# E-06_CPU_IO_PHY.net
KiCad netlist of a schematic drawn in Altium Designer
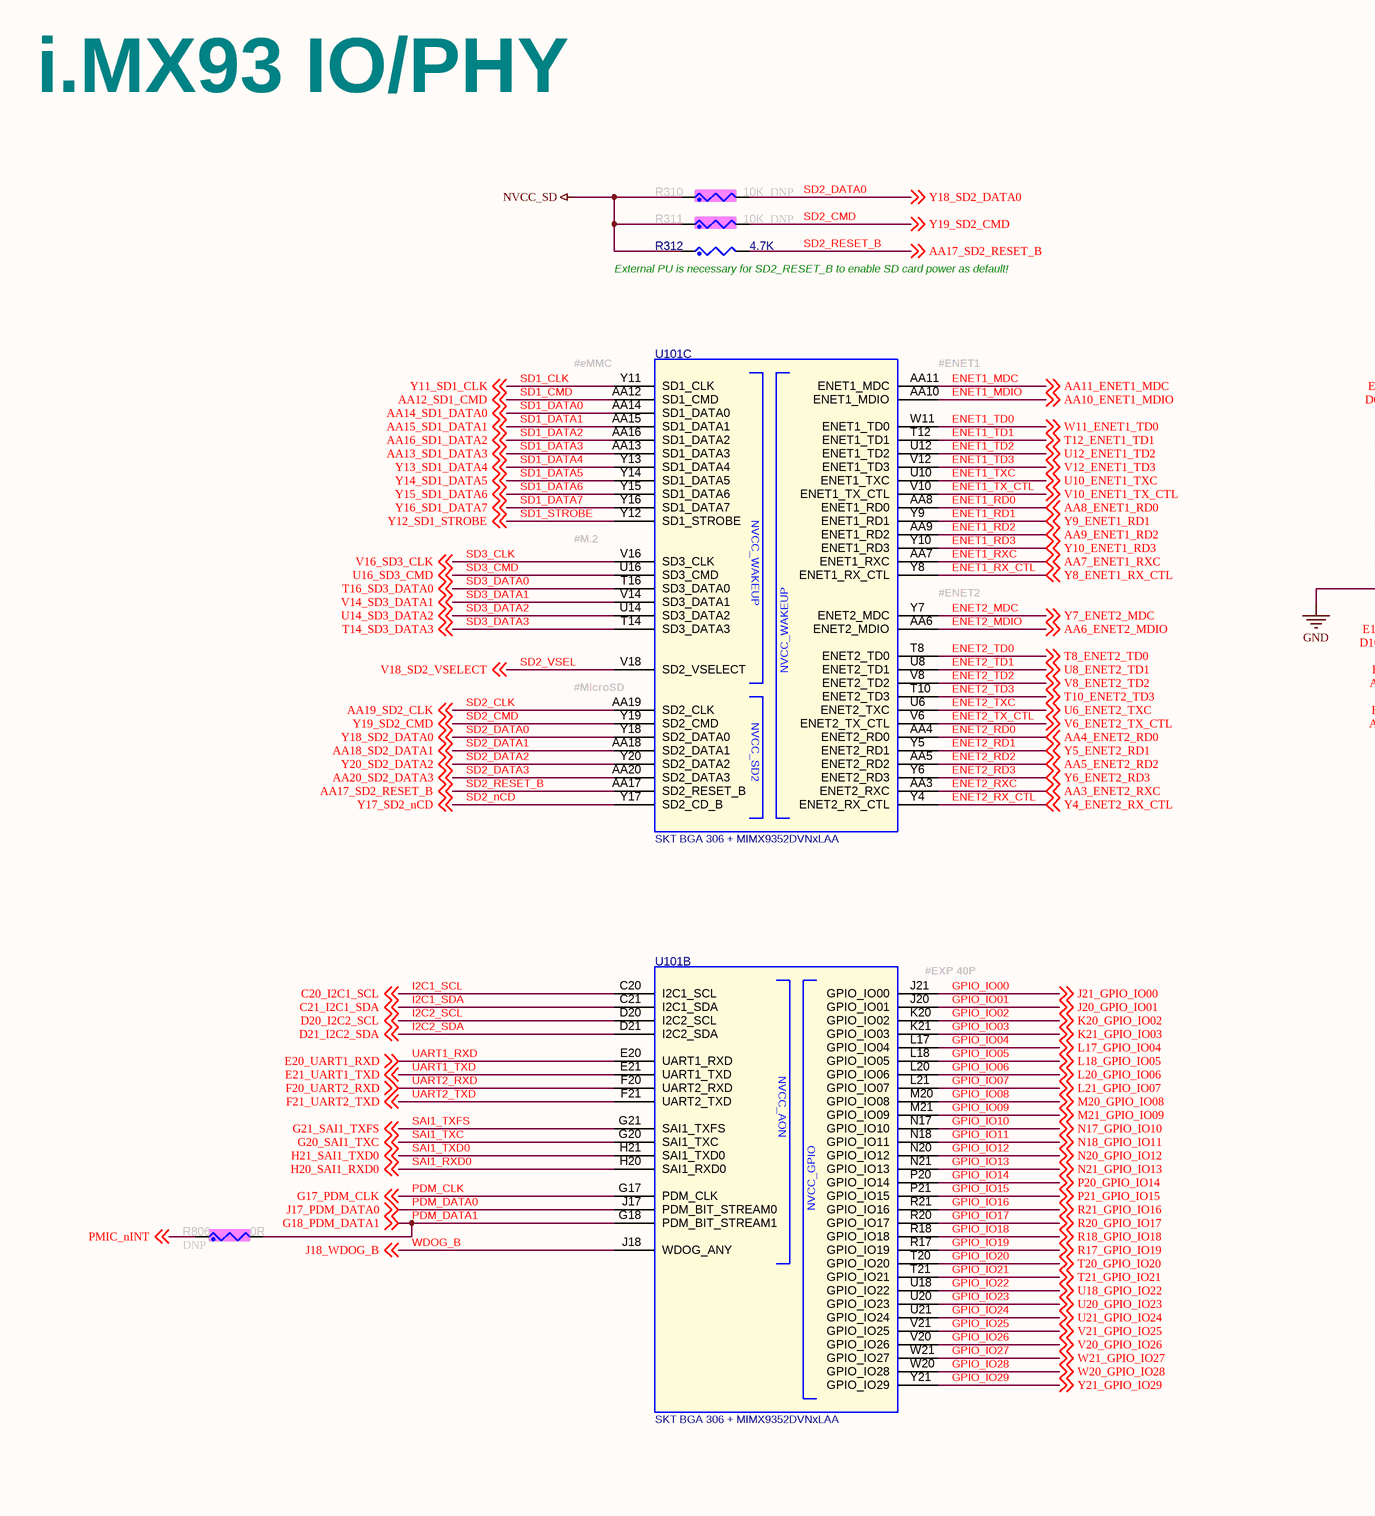
[diagram p0: E-06 CPU IO_PHY.SchDoc, left]
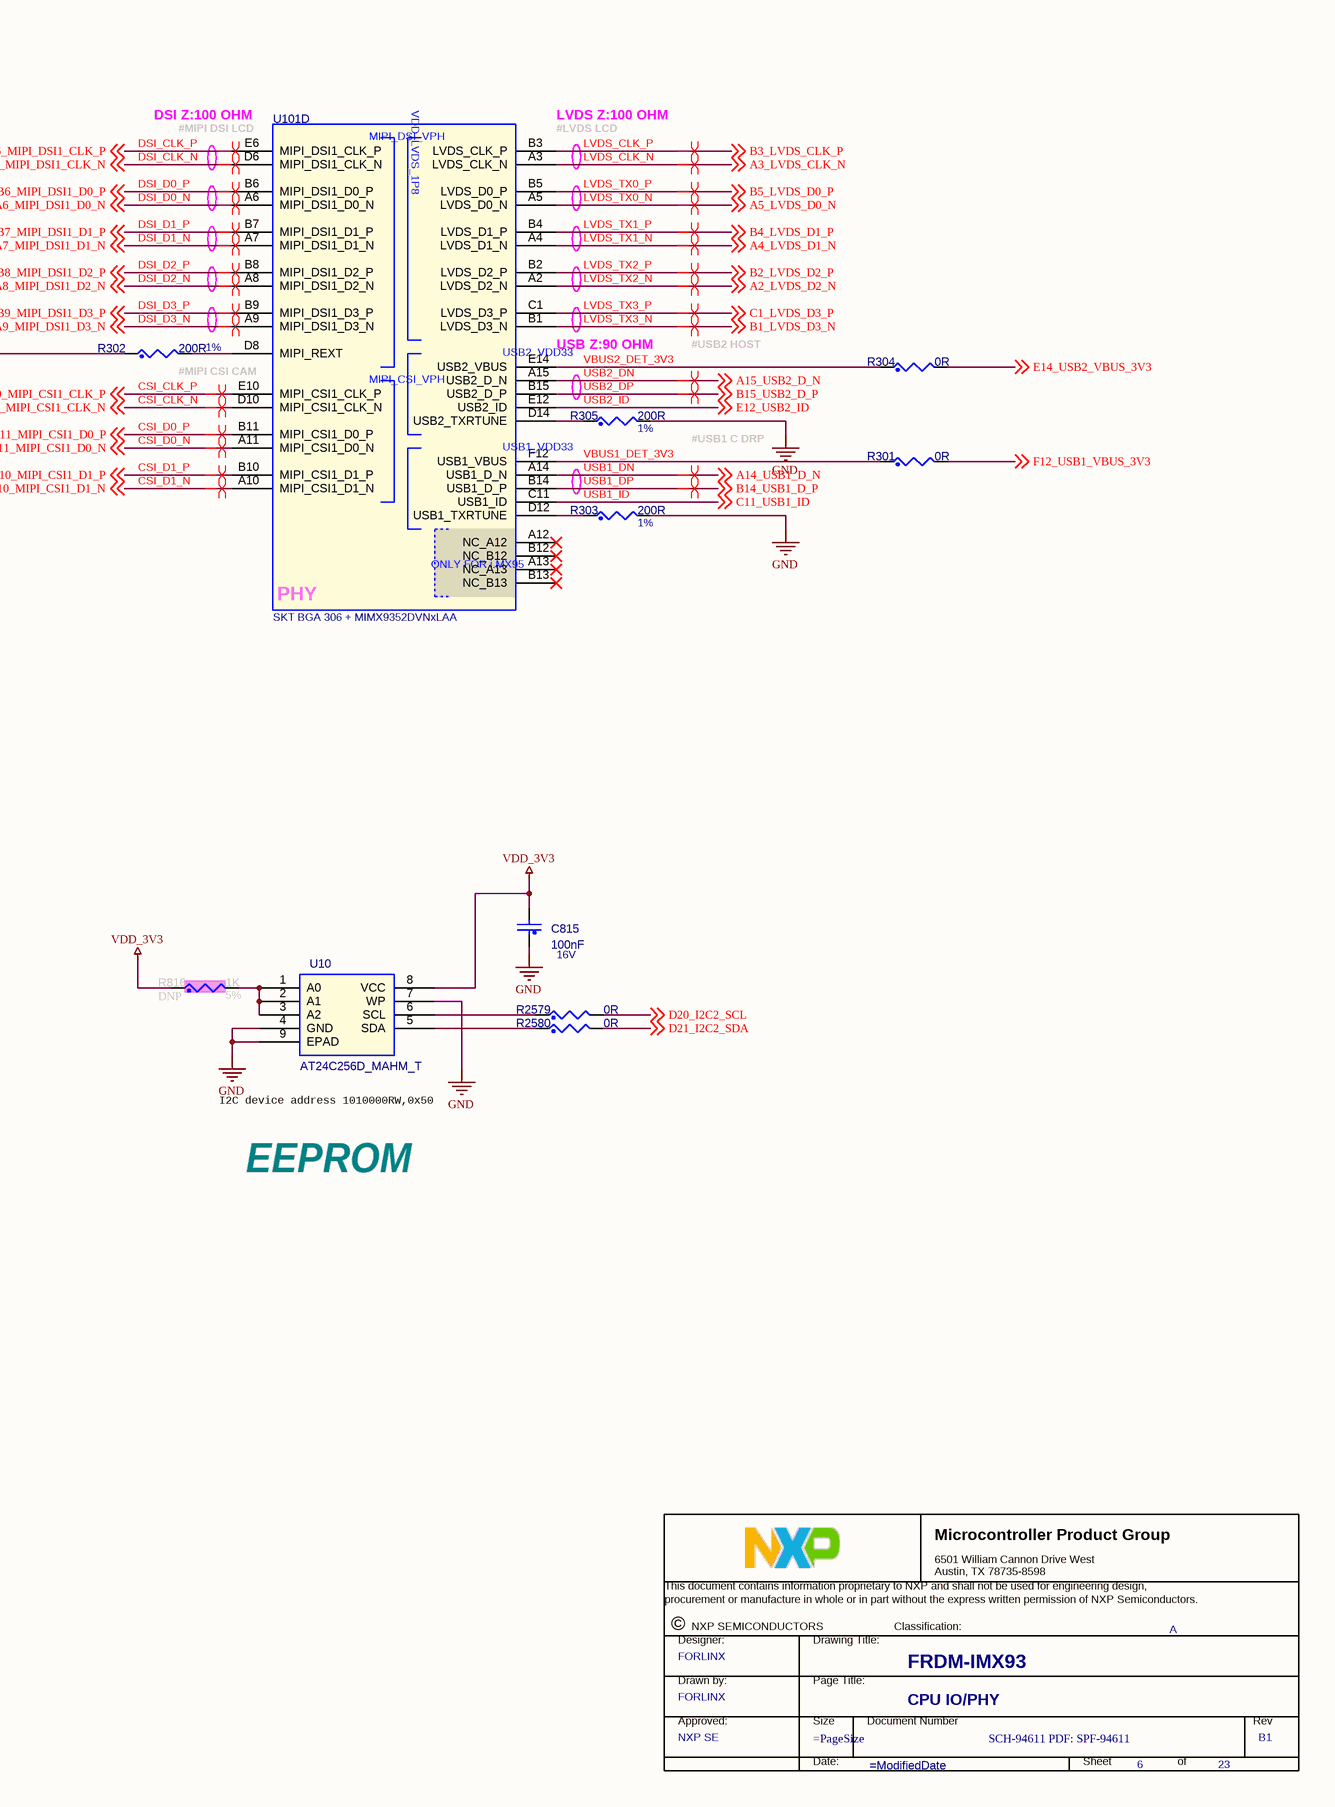
[diagram p1: E-06 CPU IO_PHY.SchDoc, right]

(export (version "E")
  (design (tool "Eeschema 10.0.6"))
  (components
    (comp (ref "C815")
      (value "100nF")
      (footprint "C0402")
      (description "0402,100nF,50V,+/-10%,X5R")
      (fields (field (name "VOLTAGE") "16V") (field (name "TOLERANCE") "10%"))
      (libsource (lib "*") (part "CAP_NP"))
    )
    (comp (ref "R301")
      (value "0R")
      (footprint "R0201")
      (description "0201,0Ohm,+/-5%")
      (libsource (lib "*") (part "RES"))
    )
    (comp (ref "R302")
      (value "200R")
      (footprint "R0201")
      (description "0201,200Ohm,+/-1%")
      (fields (field (name "VOLTAGE") "25V") (field (name "TOLERANCE") "1%"))
      (libsource (lib "*") (part "RES"))
    )
    (comp (ref "R303")
      (value "200R")
      (footprint "R0201")
      (description "0201,200Ohm,+/-1%")
      (fields (field (name "TOLERANCE") "1%") (field (name "VOLTAGE") "25V"))
      (libsource (lib "*") (part "RES"))
    )
    (comp (ref "R304")
      (value "0R")
      (footprint "R0201")
      (description "0201,0Ohm,+/-5%")
      (libsource (lib "*") (part "RES"))
    )
    (comp (ref "R305")
      (value "200R")
      (footprint "R0201")
      (description "0201,200Ohm,+/-1%")
      (fields (field (name "TOLERANCE") "1%") (field (name "VOLTAGE") "25V"))
      (libsource (lib "*") (part "RES"))
    )
    (comp (ref "R310")
      (value "10K")
      (footprint "R0402")
      (description "0402,10K,+/-1%")
      (fields (field (name "ASSY_OPT") "DNP") (field (name "TOLERANCE") "5%"))
      (libsource (lib "*") (part "RES"))
    )
    (comp (ref "R311")
      (value "10K")
      (footprint "R0402")
      (description "0402,10K,+/-1%")
      (fields (field (name "ASSY_OPT") "DNP") (field (name "TOLERANCE") "5%"))
      (libsource (lib "*") (part "RES"))
    )
    (comp (ref "R312")
      (value "4.7K")
      (footprint "R0402")
      (description "0402,4.7K,+/-1%")
      (fields (field (name "TOLERANCE") "5%") (field (name "VOLTAGE") "50V"))
      (libsource (lib "*") (part "RES"))
    )
    (comp (ref "R806")
      (value "0R")
      (footprint "R0201")
      (description "0201,0Ohm,+/-5%")
      (fields (field (name "ASSY_OPT") "DNP"))
      (libsource (lib "*") (part "RES"))
    )
    (comp (ref "R816")
      (value "1K")
      (footprint "R0402")
      (description "0402,1K,+/-1%")
      (fields (field (name "ASSY_OPT") "DNP") (field (name "TOLERANCE") "5%"))
      (libsource (lib "*") (part "RES"))
    )
    (comp (ref "R2579")
      (value "0R")
      (footprint "R0402")
      (description "0402,0Ohm,+/-1%")
      (fields (field (name "VOLTAGE") "1/16W") (field (name "TOLERANCE") "5%"))
      (libsource (lib "*") (part "RES"))
    )
    (comp (ref "R2580")
      (value "0R")
      (footprint "R0402")
      (description "0402,0Ohm,+/-1%")
      (fields (field (name "TOLERANCE") "5%") (field (name "VOLTAGE") "1/16W"))
      (libsource (lib "*") (part "RES"))
    )
    (comp (ref "U10")
      (value "AT24C256D_MAHM_T")
      (footprint "UDFN-8P")
      (description "FT24C256A-ENR-T,UDFN8")
      (libsource (lib "*") (part "AT24C64D-MA9M_0"))
    )
    (comp (ref "U101")
      (value "SKT BGA 306 + MIMX9352DVNxLAA")
      (footprint "skt_bga306_0p5_sq16p23_elast_nsp")
      (description "MIMX9352CVVXMAB,-40~105+C,11*11mm,0.5mm pitch,FCBGA,A,306pin,1.7GHz")
      (libsource (lib "") (part "MIMX9352DVNxLAA_1"))
    )
  )
  (nets
    (net (code "1") (name "/VBUS1_DET_3V3") (class "Default")
      (node (ref "R301") (pin "1") (pinfunction "1_1") (pintype "passive"))
      (node (ref "U101") (pin "F12") (pinfunction "USB1_VBUS_F12") (pintype "passive"))
    )
    (net (code "2") (name "/VBUS2_DET_3V3") (class "Default")
      (node (ref "R304") (pin "1") (pinfunction "1_1") (pintype "passive"))
      (node (ref "U101") (pin "E14") (pinfunction "USB2_VBUS_E14") (pintype "passive"))
    )
    (net (code "3") (name "A2_LVDS_D2_N") (class "Default")
      (node (ref "U101") (pin "A2") (pinfunction "LVDS_D2_N_A2") (pintype "passive"))
    )
    (net (code "4") (name "A3_LVDS_CLK_N") (class "Default")
      (node (ref "U101") (pin "A3") (pinfunction "LVDS_CLK_N_A3") (pintype "passive"))
    )
    (net (code "5") (name "A4_LVDS_D1_N") (class "Default")
      (node (ref "U101") (pin "A4") (pinfunction "LVDS_D1_N_A4") (pintype "passive"))
    )
    (net (code "6") (name "A5_LVDS_D0_N") (class "Default")
      (node (ref "U101") (pin "A5") (pinfunction "LVDS_D0_N_A5") (pintype "passive"))
    )
    (net (code "7") (name "A6_MIPI_DSI1_D0_N") (class "Default")
      (node (ref "U101") (pin "A6") (pinfunction "MIPI_DSI1_D0_N_A6") (pintype "passive"))
    )
    (net (code "8") (name "A7_MIPI_DSI1_D1_N") (class "Default")
      (node (ref "U101") (pin "A7") (pinfunction "MIPI_DSI1_D1_N_A7") (pintype "passive"))
    )
    (net (code "9") (name "A8_MIPI_DSI1_D2_N") (class "Default")
      (node (ref "U101") (pin "A8") (pinfunction "MIPI_DSI1_D2_N_A8") (pintype "passive"))
    )
    (net (code "10") (name "A9_MIPI_DSI1_D3_N") (class "Default")
      (node (ref "U101") (pin "A9") (pinfunction "MIPI_DSI1_D3_N_A9") (pintype "passive"))
    )
    (net (code "11") (name "A10_MIPI_CSI1_D1_N") (class "Default")
      (node (ref "U101") (pin "A10") (pinfunction "MIPI_CSI1_D1_N_A10") (pintype "passive"))
    )
    (net (code "12") (name "A11_MIPI_CSI1_D0_N") (class "Default")
      (node (ref "U101") (pin "A11") (pinfunction "MIPI_CSI1_D0_N_A11") (pintype "passive"))
    )
    (net (code "13") (name "A14_USB1_D_N") (class "Default")
      (node (ref "U101") (pin "A14") (pinfunction "USB1_D_N_A14") (pintype "passive"))
    )
    (net (code "14") (name "A15_USB2_D_N") (class "Default")
      (node (ref "U101") (pin "A15") (pinfunction "USB2_D_N_A15") (pintype "passive"))
    )
    (net (code "15") (name "AA3_ENET2_RXC") (class "Default")
      (node (ref "U101") (pin "AA3") (pinfunction "ENET2_RXC_AA3") (pintype "passive"))
    )
    (net (code "16") (name "AA4_ENET2_RD0") (class "Default")
      (node (ref "U101") (pin "AA4") (pinfunction "ENET2_RD0_AA4") (pintype "passive"))
    )
    (net (code "17") (name "AA5_ENET2_RD2") (class "Default")
      (node (ref "U101") (pin "AA5") (pinfunction "ENET2_RD2_AA5") (pintype "passive"))
    )
    (net (code "18") (name "AA6_ENET2_MDIO") (class "Default")
      (node (ref "U101") (pin "AA6") (pinfunction "ENET2_MDIO_AA6") (pintype "passive"))
    )
    (net (code "19") (name "AA7_ENET1_RXC") (class "Default")
      (node (ref "U101") (pin "AA7") (pinfunction "ENET1_RXC_AA7") (pintype "passive"))
    )
    (net (code "20") (name "AA8_ENET1_RD0") (class "Default")
      (node (ref "U101") (pin "AA8") (pinfunction "ENET1_RD0_AA8") (pintype "passive"))
    )
    (net (code "21") (name "AA9_ENET1_RD2") (class "Default")
      (node (ref "U101") (pin "AA9") (pinfunction "ENET1_RD2_AA9") (pintype "passive"))
    )
    (net (code "22") (name "AA10_ENET1_MDIO") (class "Default")
      (node (ref "U101") (pin "AA10") (pinfunction "ENET1_MDIO_AA10") (pintype "passive"))
    )
    (net (code "23") (name "AA11_ENET1_MDC") (class "Default")
      (node (ref "U101") (pin "AA11") (pinfunction "ENET1_MDC_AA11") (pintype "passive"))
    )
    (net (code "24") (name "AA12_SD1_CMD") (class "Default")
      (node (ref "U101") (pin "AA12") (pinfunction "SD1_CMD_AA12") (pintype "passive"))
    )
    (net (code "25") (name "AA13_SD1_DATA3") (class "Default")
      (node (ref "U101") (pin "AA13") (pinfunction "SD1_DATA3_AA13") (pintype "passive"))
    )
    (net (code "26") (name "AA14_SD1_DATA0") (class "Default")
      (node (ref "U101") (pin "AA14") (pinfunction "SD1_DATA0_AA14") (pintype "passive"))
    )
    (net (code "27") (name "AA15_SD1_DATA1") (class "Default")
      (node (ref "U101") (pin "AA15") (pinfunction "SD1_DATA1_AA15") (pintype "passive"))
    )
    (net (code "28") (name "AA16_SD1_DATA2") (class "Default")
      (node (ref "U101") (pin "AA16") (pinfunction "SD1_DATA2_AA16") (pintype "passive"))
    )
    (net (code "29") (name "AA17_SD2_RESET_B") (class "Default")
      (node (ref "R312") (pin "2") (pinfunction "2_2") (pintype "passive"))
      (node (ref "U101") (pin "AA17") (pinfunction "SD2_RESET_B_AA17") (pintype "passive"))
    )
    (net (code "30") (name "AA18_SD2_DATA1") (class "Default")
      (node (ref "U101") (pin "AA18") (pinfunction "SD2_DATA1_AA18") (pintype "passive"))
    )
    (net (code "31") (name "AA19_SD2_CLK") (class "Default")
      (node (ref "U101") (pin "AA19") (pinfunction "SD2_CLK_AA19") (pintype "passive"))
    )
    (net (code "32") (name "AA20_SD2_DATA3") (class "Default")
      (node (ref "U101") (pin "AA20") (pinfunction "SD2_DATA3_AA20") (pintype "passive"))
    )
    (net (code "33") (name "B1_LVDS_D3_N") (class "Default")
      (node (ref "U101") (pin "B1") (pinfunction "LVDS_D3_N_B1") (pintype "passive"))
    )
    (net (code "34") (name "B2_LVDS_D2_P") (class "Default")
      (node (ref "U101") (pin "B2") (pinfunction "LVDS_D2_P_B2") (pintype "passive"))
    )
    (net (code "35") (name "B3_LVDS_CLK_P") (class "Default")
      (node (ref "U101") (pin "B3") (pinfunction "LVDS_CLK_P_B3") (pintype "passive"))
    )
    (net (code "36") (name "B4_LVDS_D1_P") (class "Default")
      (node (ref "U101") (pin "B4") (pinfunction "LVDS_D1_P_B4") (pintype "passive"))
    )
    (net (code "37") (name "B5_LVDS_D0_P") (class "Default")
      (node (ref "U101") (pin "B5") (pinfunction "LVDS_D0_P_B5") (pintype "passive"))
    )
    (net (code "38") (name "B6_MIPI_DSI1_D0_P") (class "Default")
      (node (ref "U101") (pin "B6") (pinfunction "MIPI_DSI1_D0_P_B6") (pintype "passive"))
    )
    (net (code "39") (name "B7_MIPI_DSI1_D1_P") (class "Default")
      (node (ref "U101") (pin "B7") (pinfunction "MIPI_DSI1_D1_P_B7") (pintype "passive"))
    )
    (net (code "40") (name "B8_MIPI_DSI1_D2_P") (class "Default")
      (node (ref "U101") (pin "B8") (pinfunction "MIPI_DSI1_D2_P_B8") (pintype "passive"))
    )
    (net (code "41") (name "B9_MIPI_DSI1_D3_P") (class "Default")
      (node (ref "U101") (pin "B9") (pinfunction "MIPI_DSI1_D3_P_B9") (pintype "passive"))
    )
    (net (code "42") (name "B10_MIPI_CSI1_D1_P") (class "Default")
      (node (ref "U101") (pin "B10") (pinfunction "MIPI_CSI1_D1_P_B10") (pintype "passive"))
    )
    (net (code "43") (name "B11_MIPI_CSI1_D0_P") (class "Default")
      (node (ref "U101") (pin "B11") (pinfunction "MIPI_CSI1_D0_P_B11") (pintype "passive"))
    )
    (net (code "44") (name "B14_USB1_D_P") (class "Default")
      (node (ref "U101") (pin "B14") (pinfunction "USB1_D_P_B14") (pintype "passive"))
    )
    (net (code "45") (name "B15_USB2_D_P") (class "Default")
      (node (ref "U101") (pin "B15") (pinfunction "USB2_D_P_B15") (pintype "passive"))
    )
    (net (code "46") (name "C1_LVDS_D3_P") (class "Default")
      (node (ref "U101") (pin "C1") (pinfunction "LVDS_D3_P_C1") (pintype "passive"))
    )
    (net (code "47") (name "C11_USB1_ID") (class "Default")
      (node (ref "U101") (pin "C11") (pinfunction "USB1_ID_C11") (pintype "passive"))
    )
    (net (code "48") (name "C20_I2C1_SCL") (class "Default")
      (node (ref "U101") (pin "C20") (pinfunction "I2C1_SCL_C20") (pintype "passive"))
    )
    (net (code "49") (name "C21_I2C1_SDA") (class "Default")
      (node (ref "U101") (pin "C21") (pinfunction "I2C1_SDA_C21") (pintype "passive"))
    )
    (net (code "50") (name "D6_MIPI_DSI1_CLK_N") (class "Default")
      (node (ref "U101") (pin "D6") (pinfunction "MIPI_DSI1_CLK_N_D6") (pintype "passive"))
    )
    (net (code "51") (name "D10_MIPI_CSI1_CLK_N") (class "Default")
      (node (ref "U101") (pin "D10") (pinfunction "MIPI_CSI1_CLK_N_D10") (pintype "passive"))
    )
    (net (code "52") (name "D20_I2C2_SCL") (class "Default")
      (node (ref "R2579") (pin "2") (pinfunction "2_2") (pintype "passive"))
      (node (ref "U101") (pin "D20") (pinfunction "I2C2_SCL_D20") (pintype "passive"))
    )
    (net (code "53") (name "D21_I2C2_SDA") (class "Default")
      (node (ref "R2580") (pin "2") (pinfunction "2_2") (pintype "passive"))
      (node (ref "U101") (pin "D21") (pinfunction "I2C2_SDA_D21") (pintype "passive"))
    )
    (net (code "54") (name "E6_MIPI_DSI1_CLK_P") (class "Default")
      (node (ref "U101") (pin "E6") (pinfunction "MIPI_DSI1_CLK_P_E6") (pintype "passive"))
    )
    (net (code "55") (name "E10_MIPI_CSI1_CLK_P") (class "Default")
      (node (ref "U101") (pin "E10") (pinfunction "MIPI_CSI1_CLK_P_E10") (pintype "passive"))
    )
    (net (code "56") (name "E12_USB2_ID") (class "Default")
      (node (ref "U101") (pin "E12") (pinfunction "USB2_ID_E12") (pintype "passive"))
    )
    (net (code "57") (name "E14_USB2_VBUS_3V3") (class "Default")
      (node (ref "R304") (pin "2") (pinfunction "2_2") (pintype "passive"))
    )
    (net (code "58") (name "E20_UART1_RXD") (class "Default")
      (node (ref "U101") (pin "E20") (pinfunction "UART1_RXD_E20") (pintype "passive"))
    )
    (net (code "59") (name "E21_UART1_TXD") (class "Default")
      (node (ref "U101") (pin "E21") (pinfunction "UART1_TXD_E21") (pintype "passive"))
    )
    (net (code "60") (name "F12_USB1_VBUS_3V3") (class "Default")
      (node (ref "R301") (pin "2") (pinfunction "2_2") (pintype "passive"))
    )
    (net (code "61") (name "F20_UART2_RXD") (class "Default")
      (node (ref "U101") (pin "F20") (pinfunction "UART2_RXD_F20") (pintype "passive"))
    )
    (net (code "62") (name "F21_UART2_TXD") (class "Default")
      (node (ref "U101") (pin "F21") (pinfunction "UART2_TXD_F21") (pintype "passive"))
    )
    (net (code "63") (name "G17_PDM_CLK") (class "Default")
      (node (ref "U101") (pin "G17") (pinfunction "PDM_CLK_G17") (pintype "passive"))
    )
    (net (code "64") (name "G18_PDM_DATA1") (class "Default")
      (node (ref "R806") (pin "2") (pinfunction "2_2") (pintype "passive"))
      (node (ref "U101") (pin "G18") (pinfunction "PDM_BIT_STREAM1_G18") (pintype "passive"))
    )
    (net (code "65") (name "G20_SAI1_TXC") (class "Default")
      (node (ref "U101") (pin "G20") (pinfunction "SAI1_TXC_G20") (pintype "passive"))
    )
    (net (code "66") (name "G21_SAI1_TXFS") (class "Default")
      (node (ref "U101") (pin "G21") (pinfunction "SAI1_TXFS_G21") (pintype "passive"))
    )
    (net (code "67") (name "GND") (class "Default")
      (node (ref "C815") (pin "1") (pinfunction "1_1") (pintype "passive"))
      (node (ref "R302") (pin "1") (pinfunction "1_1") (pintype "passive"))
      (node (ref "R303") (pin "2") (pinfunction "2_2") (pintype "passive"))
      (node (ref "R305") (pin "2") (pinfunction "2_2") (pintype "passive"))
      (node (ref "U10") (pin "4") (pinfunction "GND_4") (pintype "passive"))
      (node (ref "U10") (pin "7") (pinfunction "WP_7") (pintype "passive"))
      (node (ref "U10") (pin "9") (pinfunction "EPAD_9") (pintype "passive"))
    )
    (net (code "68") (name "H20_SAI1_RXD0") (class "Default")
      (node (ref "U101") (pin "H20") (pinfunction "SAI1_RXD0_H20") (pintype "passive"))
    )
    (net (code "69") (name "H21_SAI1_TXD0") (class "Default")
      (node (ref "U101") (pin "H21") (pinfunction "SAI1_TXD0_H21") (pintype "passive"))
    )
    (net (code "70") (name "J17_PDM_DATA0") (class "Default")
      (node (ref "U101") (pin "J17") (pinfunction "PDM_BIT_STREAM0_J17") (pintype "passive"))
    )
    (net (code "71") (name "J18_WDOG_B") (class "Default")
      (node (ref "U101") (pin "J18") (pinfunction "WDOG_ANY_J18") (pintype "passive"))
    )
    (net (code "72") (name "J20_GPIO_IO01") (class "Default")
      (node (ref "U101") (pin "J20") (pinfunction "GPIO_IO01_J20") (pintype "passive"))
    )
    (net (code "73") (name "J21_GPIO_IO00") (class "Default")
      (node (ref "U101") (pin "J21") (pinfunction "GPIO_IO00_J21") (pintype "passive"))
    )
    (net (code "74") (name "K20_GPIO_IO02") (class "Default")
      (node (ref "U101") (pin "K20") (pinfunction "GPIO_IO02_K20") (pintype "passive"))
    )
    (net (code "75") (name "K21_GPIO_IO03") (class "Default")
      (node (ref "U101") (pin "K21") (pinfunction "GPIO_IO03_K21") (pintype "passive"))
    )
    (net (code "76") (name "L17_GPIO_IO04") (class "Default")
      (node (ref "U101") (pin "L17") (pinfunction "GPIO_IO04_L17") (pintype "passive"))
    )
    (net (code "77") (name "L18_GPIO_IO05") (class "Default")
      (node (ref "U101") (pin "L18") (pinfunction "GPIO_IO05_L18") (pintype "passive"))
    )
    (net (code "78") (name "L20_GPIO_IO06") (class "Default")
      (node (ref "U101") (pin "L20") (pinfunction "GPIO_IO06_L20") (pintype "passive"))
    )
    (net (code "79") (name "L21_GPIO_IO07") (class "Default")
      (node (ref "U101") (pin "L21") (pinfunction "GPIO_IO07_L21") (pintype "passive"))
    )
    (net (code "80") (name "M20_GPIO_IO08") (class "Default")
      (node (ref "U101") (pin "M20") (pinfunction "GPIO_IO08_M20") (pintype "passive"))
    )
    (net (code "81") (name "M21_GPIO_IO09") (class "Default")
      (node (ref "U101") (pin "M21") (pinfunction "GPIO_IO09_M21") (pintype "passive"))
    )
    (net (code "82") (name "N17_GPIO_IO10") (class "Default")
      (node (ref "U101") (pin "N17") (pinfunction "GPIO_IO10_N17") (pintype "passive"))
    )
    (net (code "83") (name "N18_GPIO_IO11") (class "Default")
      (node (ref "U101") (pin "N18") (pinfunction "GPIO_IO11_N18") (pintype "passive"))
    )
    (net (code "84") (name "N20_GPIO_IO12") (class "Default")
      (node (ref "U101") (pin "N20") (pinfunction "GPIO_IO12_N20") (pintype "passive"))
    )
    (net (code "85") (name "N21_GPIO_IO13") (class "Default")
      (node (ref "U101") (pin "N21") (pinfunction "GPIO_IO13_N21") (pintype "passive"))
    )
    (net (code "86") (name "NVCC_SD") (class "Default")
      (node (ref "R310") (pin "1") (pinfunction "1_1") (pintype "passive"))
      (node (ref "R311") (pin "1") (pinfunction "1_1") (pintype "passive"))
      (node (ref "R312") (pin "1") (pinfunction "1_1") (pintype "passive"))
    )
    (net (code "87") (name "Net-(U10-A0)") (class "Default")
      (node (ref "R816") (pin "2") (pinfunction "2_2") (pintype "passive"))
      (node (ref "U10") (pin "1") (pinfunction "A0_1") (pintype "passive"))
      (node (ref "U10") (pin "2") (pinfunction "A1_2") (pintype "passive"))
      (node (ref "U10") (pin "3") (pinfunction "A2_3") (pintype "passive"))
    )
    (net (code "88") (name "Net-(U10-SCL)") (class "Default")
      (node (ref "R2579") (pin "1") (pinfunction "1_1") (pintype "passive"))
      (node (ref "U10") (pin "6") (pinfunction "SCL_6") (pintype "passive"))
    )
    (net (code "89") (name "Net-(U10-SDA)") (class "Default")
      (node (ref "R2580") (pin "1") (pinfunction "1_1") (pintype "passive"))
      (node (ref "U10") (pin "5") (pinfunction "SDA_5") (pintype "passive"))
    )
    (net (code "90") (name "Net-(U101D-MIPI_REXT)") (class "Default")
      (node (ref "R302") (pin "2") (pinfunction "2_2") (pintype "passive"))
      (node (ref "U101") (pin "D8") (pinfunction "MIPI_REXT_D8") (pintype "passive"))
    )
    (net (code "91") (name "Net-(U101D-USB1_TXRTUNE)") (class "Default")
      (node (ref "R303") (pin "1") (pinfunction "1_1") (pintype "passive"))
      (node (ref "U101") (pin "D12") (pinfunction "USB1_TXRTUNE_D12") (pintype "passive"))
    )
    (net (code "92") (name "Net-(U101D-USB2_TXRTUNE)") (class "Default")
      (node (ref "R305") (pin "1") (pinfunction "1_1") (pintype "passive"))
      (node (ref "U101") (pin "D14") (pinfunction "USB2_TXRTUNE_D14") (pintype "passive"))
    )
    (net (code "93") (name "P20_GPIO_IO14") (class "Default")
      (node (ref "U101") (pin "P20") (pinfunction "GPIO_IO14_P20") (pintype "passive"))
    )
    (net (code "94") (name "P21_GPIO_IO15") (class "Default")
      (node (ref "U101") (pin "P21") (pinfunction "GPIO_IO15_P21") (pintype "passive"))
    )
    (net (code "95") (name "PMIC_nINT") (class "Default")
      (node (ref "R806") (pin "1") (pinfunction "1_1") (pintype "passive"))
    )
    (net (code "96") (name "R17_GPIO_IO19") (class "Default")
      (node (ref "U101") (pin "R17") (pinfunction "GPIO_IO19_R17") (pintype "passive"))
    )
    (net (code "97") (name "R18_GPIO_IO18") (class "Default")
      (node (ref "U101") (pin "R18") (pinfunction "GPIO_IO18_R18") (pintype "passive"))
    )
    (net (code "98") (name "R20_GPIO_IO17") (class "Default")
      (node (ref "U101") (pin "R20") (pinfunction "GPIO_IO17_R20") (pintype "passive"))
    )
    (net (code "99") (name "R21_GPIO_IO16") (class "Default")
      (node (ref "U101") (pin "R21") (pinfunction "GPIO_IO16_R21") (pintype "passive"))
    )
    (net (code "100") (name "T8_ENET2_TD0") (class "Default")
      (node (ref "U101") (pin "T8") (pinfunction "ENET2_TD0_T8") (pintype "passive"))
    )
    (net (code "101") (name "T10_ENET2_TD3") (class "Default")
      (node (ref "U101") (pin "T10") (pinfunction "ENET2_TD3_T10") (pintype "passive"))
    )
    (net (code "102") (name "T12_ENET1_TD1") (class "Default")
      (node (ref "U101") (pin "T12") (pinfunction "ENET1_TD1_T12") (pintype "passive"))
    )
    (net (code "103") (name "T14_SD3_DATA3") (class "Default")
      (node (ref "U101") (pin "T14") (pinfunction "SD3_DATA3_T14") (pintype "passive"))
    )
    (net (code "104") (name "T16_SD3_DATA0") (class "Default")
      (node (ref "U101") (pin "T16") (pinfunction "SD3_DATA0_T16") (pintype "passive"))
    )
    (net (code "105") (name "T20_GPIO_IO20") (class "Default")
      (node (ref "U101") (pin "T20") (pinfunction "GPIO_IO20_T20") (pintype "passive"))
    )
    (net (code "106") (name "T21_GPIO_IO21") (class "Default")
      (node (ref "U101") (pin "T21") (pinfunction "GPIO_IO21_T21") (pintype "passive"))
    )
    (net (code "107") (name "U6_ENET2_TXC") (class "Default")
      (node (ref "U101") (pin "U6") (pinfunction "ENET2_TXC_U6") (pintype "passive"))
    )
    (net (code "108") (name "U8_ENET2_TD1") (class "Default")
      (node (ref "U101") (pin "U8") (pinfunction "ENET2_TD1_U8") (pintype "passive"))
    )
    (net (code "109") (name "U10_ENET1_TXC") (class "Default")
      (node (ref "U101") (pin "U10") (pinfunction "ENET1_TXC_U10") (pintype "passive"))
    )
    (net (code "110") (name "U12_ENET1_TD2") (class "Default")
      (node (ref "U101") (pin "U12") (pinfunction "ENET1_TD2_U12") (pintype "passive"))
    )
    (net (code "111") (name "U14_SD3_DATA2") (class "Default")
      (node (ref "U101") (pin "U14") (pinfunction "SD3_DATA2_U14") (pintype "passive"))
    )
    (net (code "112") (name "U16_SD3_CMD") (class "Default")
      (node (ref "U101") (pin "U16") (pinfunction "SD3_CMD_U16") (pintype "passive"))
    )
    (net (code "113") (name "U18_GPIO_IO22") (class "Default")
      (node (ref "U101") (pin "U18") (pinfunction "GPIO_IO22_U18") (pintype "passive"))
    )
    (net (code "114") (name "U20_GPIO_IO23") (class "Default")
      (node (ref "U101") (pin "U20") (pinfunction "GPIO_IO23_U20") (pintype "passive"))
    )
    (net (code "115") (name "U21_GPIO_IO24") (class "Default")
      (node (ref "U101") (pin "U21") (pinfunction "GPIO_IO24_U21") (pintype "passive"))
    )
    (net (code "116") (name "V6_ENET2_TX_CTL") (class "Default")
      (node (ref "U101") (pin "V6") (pinfunction "ENET2_TX_CTL_V6") (pintype "passive"))
    )
    (net (code "117") (name "V8_ENET2_TD2") (class "Default")
      (node (ref "U101") (pin "V8") (pinfunction "ENET2_TD2_V8") (pintype "passive"))
    )
    (net (code "118") (name "V10_ENET1_TX_CTL") (class "Default")
      (node (ref "U101") (pin "V10") (pinfunction "ENET1_TX_CTL_V10") (pintype "passive"))
    )
    (net (code "119") (name "V12_ENET1_TD3") (class "Default")
      (node (ref "U101") (pin "V12") (pinfunction "ENET1_TD3_V12") (pintype "passive"))
    )
    (net (code "120") (name "V14_SD3_DATA1") (class "Default")
      (node (ref "U101") (pin "V14") (pinfunction "SD3_DATA1_V14") (pintype "passive"))
    )
    (net (code "121") (name "V16_SD3_CLK") (class "Default")
      (node (ref "U101") (pin "V16") (pinfunction "SD3_CLK_V16") (pintype "passive"))
    )
    (net (code "122") (name "V18_SD2_VSELECT") (class "Default")
      (node (ref "U101") (pin "V18") (pinfunction "SD2_VSELECT_V18") (pintype "passive"))
    )
    (net (code "123") (name "V20_GPIO_IO26") (class "Default")
      (node (ref "U101") (pin "V20") (pinfunction "GPIO_IO26_V20") (pintype "passive"))
    )
    (net (code "124") (name "V21_GPIO_IO25") (class "Default")
      (node (ref "U101") (pin "V21") (pinfunction "GPIO_IO25_V21") (pintype "passive"))
    )
    (net (code "125") (name "VDD_3V3") (class "Default")
      (node (ref "C815") (pin "2") (pinfunction "2_2") (pintype "passive"))
      (node (ref "R816") (pin "1") (pinfunction "1_1") (pintype "passive"))
      (node (ref "U10") (pin "8") (pinfunction "VCC_8") (pintype "passive"))
    )
    (net (code "126") (name "W11_ENET1_TD0") (class "Default")
      (node (ref "U101") (pin "W11") (pinfunction "ENET1_TD0_W11") (pintype "passive"))
    )
    (net (code "127") (name "W20_GPIO_IO28") (class "Default")
      (node (ref "U101") (pin "W20") (pinfunction "GPIO_IO28_W20") (pintype "passive"))
    )
    (net (code "128") (name "W21_GPIO_IO27") (class "Default")
      (node (ref "U101") (pin "W21") (pinfunction "GPIO_IO27_W21") (pintype "passive"))
    )
    (net (code "129") (name "Y4_ENET2_RX_CTL") (class "Default")
      (node (ref "U101") (pin "Y4") (pinfunction "ENET2_RX_CTL_Y4") (pintype "passive"))
    )
    (net (code "130") (name "Y5_ENET2_RD1") (class "Default")
      (node (ref "U101") (pin "Y5") (pinfunction "ENET2_RD1_Y5") (pintype "passive"))
    )
    (net (code "131") (name "Y6_ENET2_RD3") (class "Default")
      (node (ref "U101") (pin "Y6") (pinfunction "ENET2_RD3_Y6") (pintype "passive"))
    )
    (net (code "132") (name "Y7_ENET2_MDC") (class "Default")
      (node (ref "U101") (pin "Y7") (pinfunction "ENET2_MDC_Y7") (pintype "passive"))
    )
    (net (code "133") (name "Y8_ENET1_RX_CTL") (class "Default")
      (node (ref "U101") (pin "Y8") (pinfunction "ENET1_RX_CTL_Y8") (pintype "passive"))
    )
    (net (code "134") (name "Y9_ENET1_RD1") (class "Default")
      (node (ref "U101") (pin "Y9") (pinfunction "ENET1_RD1_Y9") (pintype "passive"))
    )
    (net (code "135") (name "Y10_ENET1_RD3") (class "Default")
      (node (ref "U101") (pin "Y10") (pinfunction "ENET1_RD3_Y10") (pintype "passive"))
    )
    (net (code "136") (name "Y11_SD1_CLK") (class "Default")
      (node (ref "U101") (pin "Y11") (pinfunction "SD1_CLK_Y11") (pintype "passive"))
    )
    (net (code "137") (name "Y12_SD1_STROBE") (class "Default")
      (node (ref "U101") (pin "Y12") (pinfunction "SD1_STROBE_Y12") (pintype "passive"))
    )
    (net (code "138") (name "Y13_SD1_DATA4") (class "Default")
      (node (ref "U101") (pin "Y13") (pinfunction "SD1_DATA4_Y13") (pintype "passive"))
    )
    (net (code "139") (name "Y14_SD1_DATA5") (class "Default")
      (node (ref "U101") (pin "Y14") (pinfunction "SD1_DATA5_Y14") (pintype "passive"))
    )
    (net (code "140") (name "Y15_SD1_DATA6") (class "Default")
      (node (ref "U101") (pin "Y15") (pinfunction "SD1_DATA6_Y15") (pintype "passive"))
    )
    (net (code "141") (name "Y16_SD1_DATA7") (class "Default")
      (node (ref "U101") (pin "Y16") (pinfunction "SD1_DATA7_Y16") (pintype "passive"))
    )
    (net (code "142") (name "Y17_SD2_nCD") (class "Default")
      (node (ref "U101") (pin "Y17") (pinfunction "SD2_CD_B_Y17") (pintype "passive"))
    )
    (net (code "143") (name "Y18_SD2_DATA0") (class "Default")
      (node (ref "R310") (pin "2") (pinfunction "2_2") (pintype "passive"))
      (node (ref "U101") (pin "Y18") (pinfunction "SD2_DATA0_Y18") (pintype "passive"))
    )
    (net (code "144") (name "Y19_SD2_CMD") (class "Default")
      (node (ref "R311") (pin "2") (pinfunction "2_2") (pintype "passive"))
      (node (ref "U101") (pin "Y19") (pinfunction "SD2_CMD_Y19") (pintype "passive"))
    )
    (net (code "145") (name "Y20_SD2_DATA2") (class "Default")
      (node (ref "U101") (pin "Y20") (pinfunction "SD2_DATA2_Y20") (pintype "passive"))
    )
    (net (code "146") (name "Y21_GPIO_IO29") (class "Default")
      (node (ref "U101") (pin "Y21") (pinfunction "GPIO_IO29_Y21") (pintype "passive"))
    )
    (net (code "147") (name "unconnected-(U101D-NC_A12-PadA12)") (class "Default")
      (node (ref "U101") (pin "A12") (pinfunction "NC_A12_A12") (pintype "passive+no_connect"))
    )
    (net (code "148") (name "unconnected-(U101D-NC_A13-PadA13)") (class "Default")
      (node (ref "U101") (pin "A13") (pinfunction "NC_A13_A13") (pintype "passive+no_connect"))
    )
    (net (code "149") (name "unconnected-(U101D-NC_B12-PadB12)") (class "Default")
      (node (ref "U101") (pin "B12") (pinfunction "NC_B12_B12") (pintype "passive+no_connect"))
    )
    (net (code "150") (name "unconnected-(U101D-NC_B13-PadB13)") (class "Default")
      (node (ref "U101") (pin "B13") (pinfunction "NC_B13_B13") (pintype "passive+no_connect"))
    )
  )
)
